# 03_-_CONNECTOR.net
KiCad netlist of a schematic drawn in Altium Designer
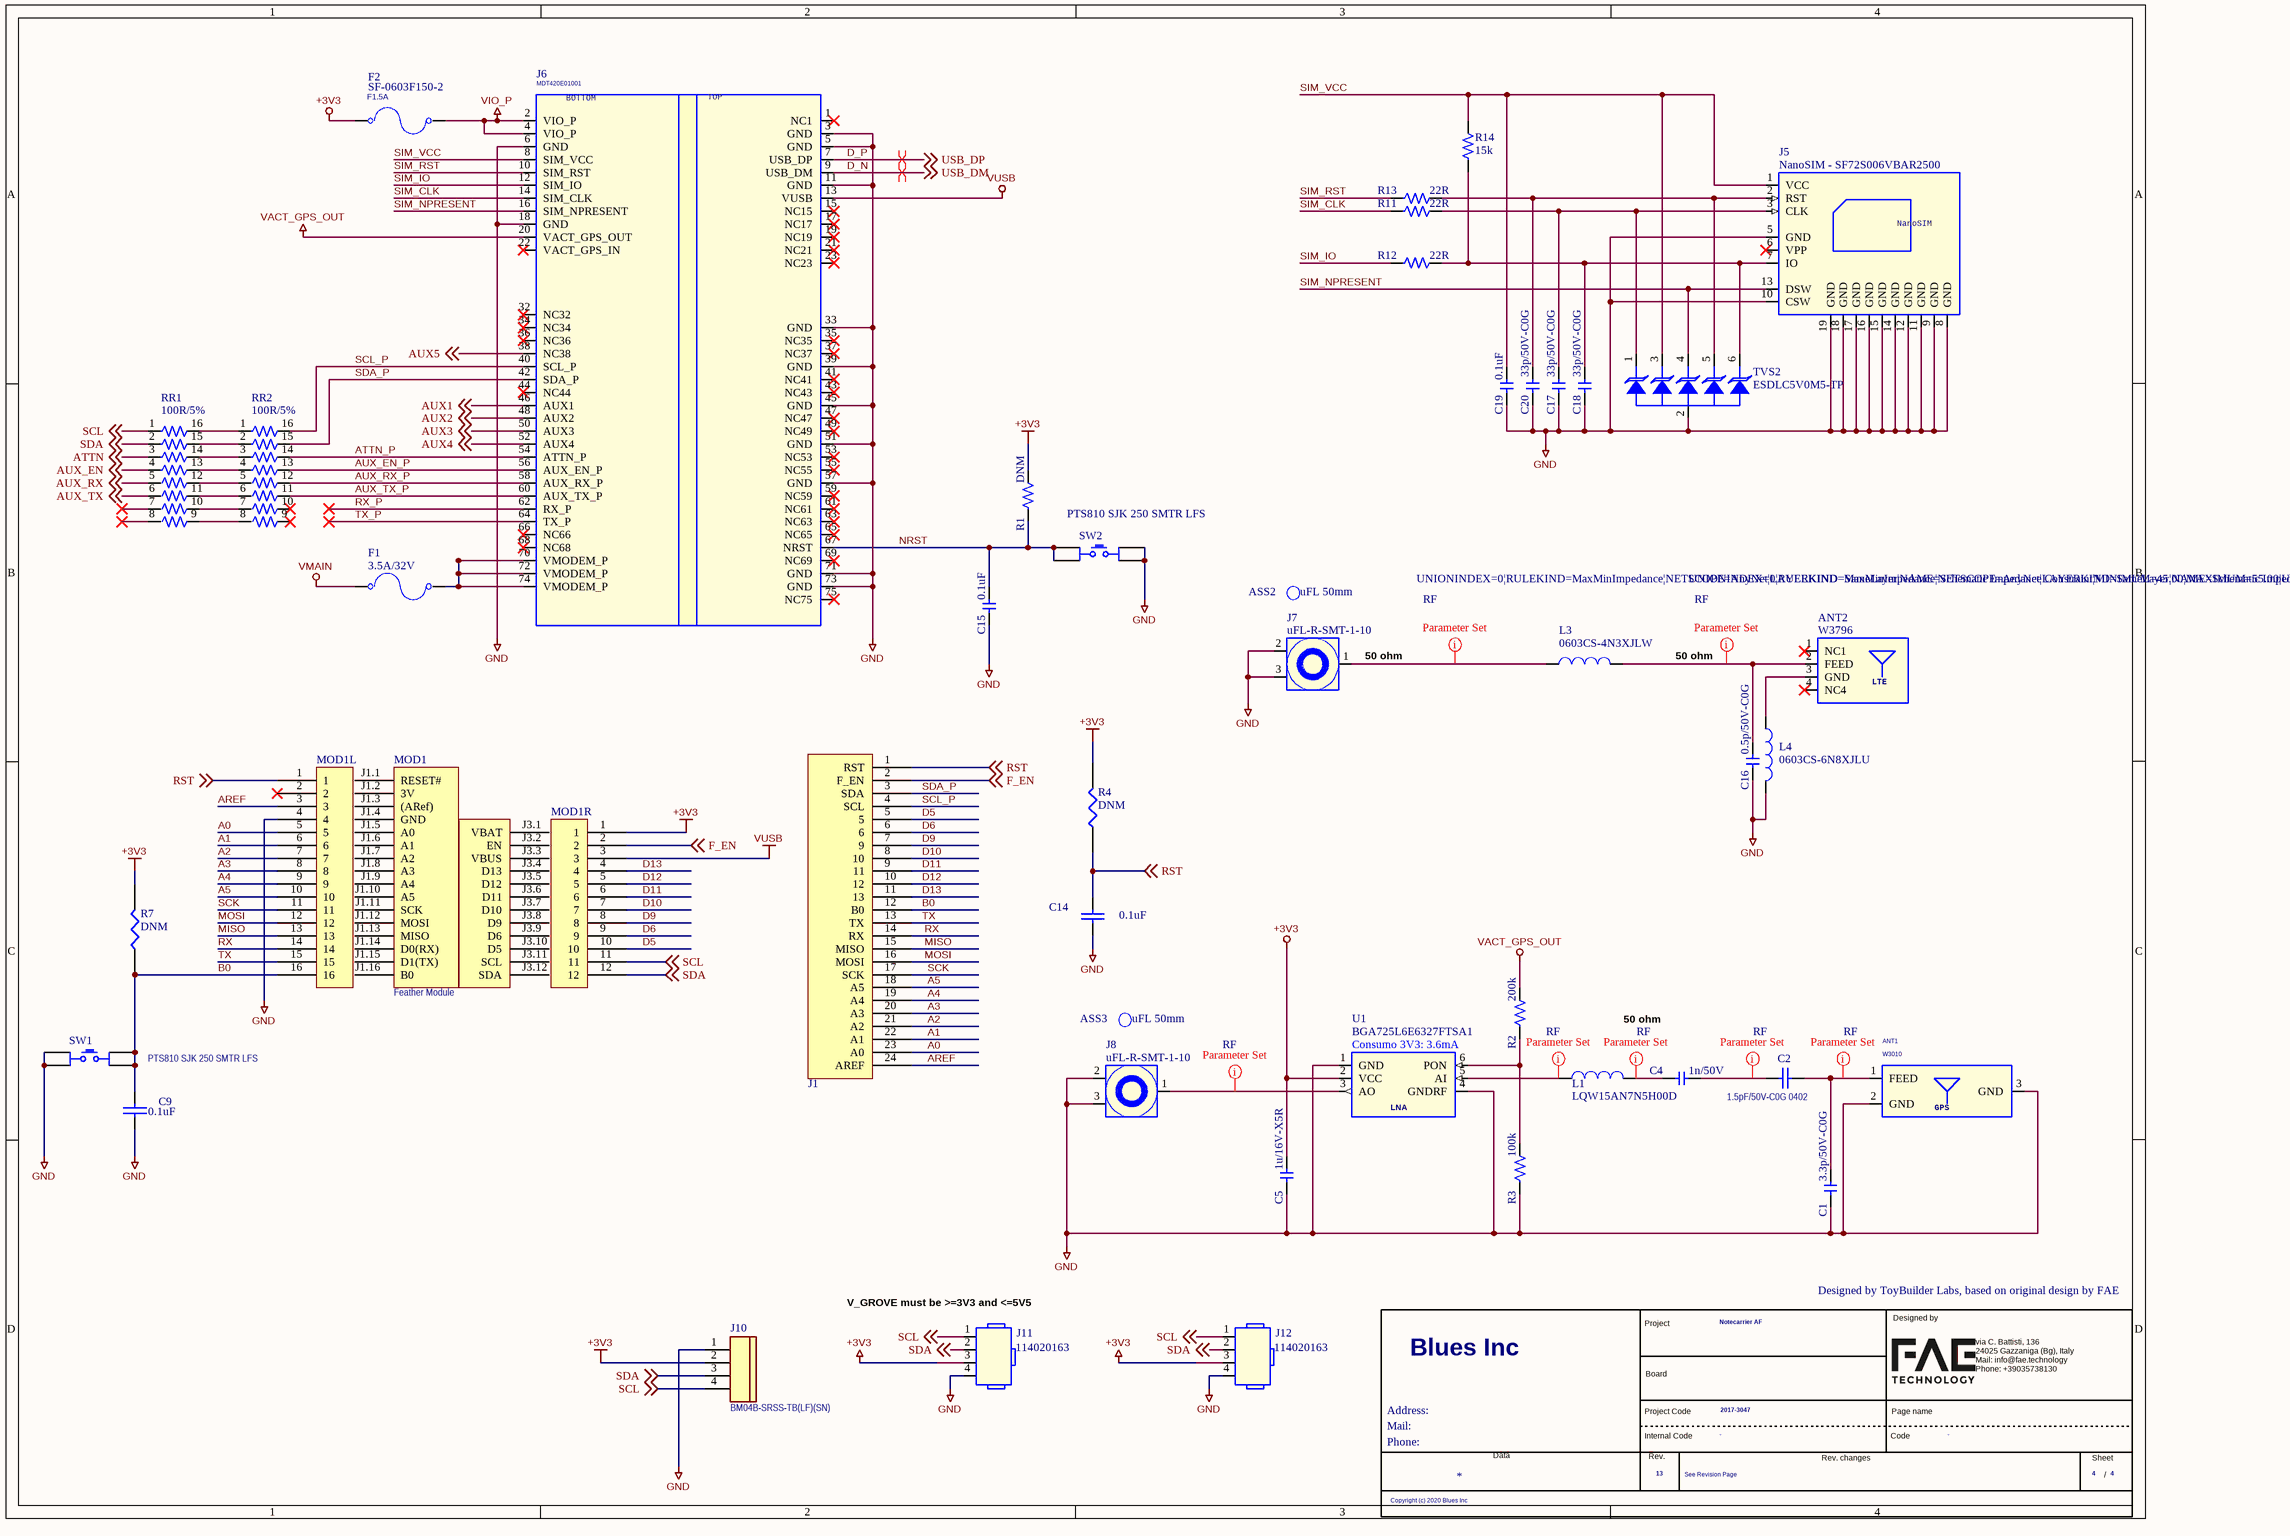
[diagram p0: 03 - CONNECTOR.SchDoc]

(export (version "E")
  (design (tool "Eeschema 10.0.6"))
  (components
    (comp (ref "*")
      (value "MyBlues")
      (fields
        (field (name "ADDRESS") "Address:")
        (field (name "COPYRIGHT") "Copyright (c) 2020 Blues Inc")
        (field (name "CUSTOMER CODE") "-")
        (field (name "CUSTOMERNAME") "Blues Inc")
        (field (name "DATABASE") "-")
        (field (name "DOCUMENTOREV") "See Revision Page")
        (field (name "MAIL") "Mail:")
        (field (name "NOME PROGETTO") "Notecarrier AF")
        (field (name "PAGE COUNT") "4")
        (field (name "PAGE NUMBER") "4")
        (field (name "PHONE") "Phone:")
        (field (name "PROJECT CODE") "2017-3047")
        (field (name "REVISION") "13")
      )
      (libsource (lib "*") (part "MyBlues"))
    )
    (comp (ref "ANT1")
      (value "W3010")
      (footprint "ANT-W3010")
      (description "ANTENNA CHIP 1.575GHZ D=3.2X10X2 W3010 PULSE SMT")
      (libsource (lib "*") (part "ANT - W3010 - GPS-GLONASS"))
    )
    (comp (ref "ANT2")
      (value "W3796")
      (footprint "ANT-W3796")
      (description "ANTENNA CHIP LTE D=40X7X3 W3796 PULSE SMT")
      (libsource (lib "*") (part "ANT - W3796 - LTE"))
    )
    (comp (ref "ASS2")
      (value "uFL 50mm")
      (description "CAVO COAX uFl-uFl 415-0086-050 HIROSE CINCH CONNECTIVITY SOLUTIONS JOHNSON")
      (libsource (lib "*") (part "0000_BASE SIMBOLO_OBJ"))
    )
    (comp (ref "ASS3")
      (value "uFL 50mm")
      (description "CAVO COAX uFl-uFl 415-0086-050 HIROSE CINCH CONNECTIVITY SOLUTIONS JOHNSON")
      (libsource (lib "*") (part "0000_BASE SIMBOLO_OBJ"))
    )
    (comp (ref "C1")
      (value "3.3p/50V-C0G")
      (footprint "CS-C-0402")
      (description "CHIP CAP.CER. 3.3pF 50V 5% C0G 0402")
      (libsource (lib "*") (part "CS-C-0402-3.3p/50V-C0G"))
    )
    (comp (ref "C2")
      (value "1.5pF/50V-C0G 0402")
      (footprint "CAPC1005X55X25NL05T10")
      (fields (field (name "PART NUMBER") "GJM1555C1H1R5BB01D") (field (name "MANUFACTURER") "Murata"))
      (libsource (lib "Altium Content Vault") (part "CAP"))
    )
    (comp (ref "C4")
      (value "1n/50V")
      (footprint "CS-C-0402")
      (description "CHIP CAP.CER. 1nF 50V 10% X7R 0402")
      (libsource (lib "*") (part "CS-C-0402-1n/50V"))
    )
    (comp (ref "C5")
      (value "1u/16V-X5R")
      (footprint "CS-C-0402")
      (description "CHIP CAP.CER. 1uF 16V 10% X5R 0402")
      (libsource (lib "*") (part "CS-C-0402-1u/16-X5R"))
    )
    (comp (ref "C9")
      (value "0.1uF")
      (footprint "CS-C-0402")
      (description "CHIP CAP.CER. 100nF 16V 10% X7R 0402")
      (fields (field (name "MFR") "Yageo"))
      (libsource (lib "Cap_SCH") (part "CAP"))
    )
    (comp (ref "C14")
      (value "0.1uF")
      (footprint "CS-C-0402")
      (description "CHIP CAP.CER. 100nF 16V 10% X7R 0402")
      (fields (field (name "MFR") "Yageo"))
      (libsource (lib "Cap_SCH") (part "CAP"))
    )
    (comp (ref "C15")
      (value "0.1uF")
      (footprint "CS-C-0402")
      (description "CHIP CAP.CER. 100nF 16V 10% X7R 0402")
      (fields (field (name "MFR") "Yageo"))
      (libsource (lib "*") (part "CS-C-0402-100n/16V"))
    )
    (comp (ref "C16")
      (value "0.5p/50V-C0G")
      (footprint "CS-C-0402")
      (description "CHIP CAP.CER. 0.5pF 50V ±0.25 C0G 0402 GRM1555C1HR50CA01D MURATA")
      (libsource (lib "*") (part "CS-C-0402-0.5p/50V-C0G"))
    )
    (comp (ref "C17")
      (value "33p/50V-C0G")
      (footprint "CS-C-0402")
      (description "CHIP CAP.CER. 33pF 50V 5% C0G 0402")
      (libsource (lib "*") (part "CS-C-0402-33p/50V-C0G"))
    )
    (comp (ref "C18")
      (value "33p/50V-C0G")
      (footprint "CS-C-0402")
      (description "CHIP CAP.CER. 33pF 50V 5% C0G 0402")
      (libsource (lib "*") (part "CS-C-0402-33p/50V-C0G"))
    )
    (comp (ref "C19")
      (value "0.1uF")
      (footprint "CS-C-0402")
      (description "CHIP CAP.CER. 100nF 16V 10% X7R 0402")
      (fields (field (name "MFR") "Yageo"))
      (libsource (lib "*") (part "CS-C-0402-100n/16V"))
    )
    (comp (ref "C20")
      (value "33p/50V-C0G")
      (footprint "CS-C-0402")
      (description "CHIP CAP.CER. 33pF 50V 5% C0G 0402")
      (libsource (lib "*") (part "CS-C-0402-33p/50V-C0G"))
    )
    (comp (ref "F1")
      (value "3.5A/32V")
      (footprint "FS-0603")
      (description "FUSIBILE RAPIDO 3.5A 32V 0603 0603SFV350F/32-2 LITTELFUSE SMT")
      (fields (field (name "MPN") "0603SFV350F/32-2"))
      (libsource (lib "*") (part "RAPIDO - 0603SFV350F- 3.5A/32V"))
    )
    (comp (ref "F2")
      (value "SF-0603F150-2")
      (footprint "FS-0603")
      (description "FUSIBILE RAPIDO 1.5A 32V 0603 SF-0603F150-2 BOURNS SMT")
      (libsource (lib "*") (part "RAPIDO - SF-0603F150-2-1.5A/32V"))
    )
    (comp (ref "J1")
      (value "12X1")
      (footprint "WE24S - 2.54")
      (libsource (lib "ATA_BLS_002_NTCR_A0-01_SCHLIB") (part "SIDECON"))
    )
    (comp (ref "J5")
      (value "NanoSIM - SF72S006VBAR2500")
      (footprint "J-NANOSIM-SF72S006VBA")
      (description "CONN. NANOSIM 8P F/90° PUSH-PUSH SF72S006VBAR2500 JAE ELECTRONICS SMT")
      (libsource (lib "*") (part "NANOSIM - J-NANOSIM-SF72S006VBA"))
    )
    (comp (ref "J6")
      (value "MDT420E01001")
      (footprint "J-75-0050-MOS-M2-E")
      (description "CONN. M.2 75P M/90° P=0.5 MDT420E01001 AMPHENOL SMT")
      (libsource (lib "*") (part "AMPHENOL-75 - M-2 KEY E_13"))
    )
    (comp (ref "J7")
      (value "uFL-R-SMT-1-10")
      (footprint "J-3-MDS-UFL")
      (description "CONN. RF M U.FL-R-SMT-1(10) HIROSE SMT")
      (libsource (lib "*") (part "UFL - U-FL-R-SMT-1-10"))
    )
    (comp (ref "J8")
      (value "uFL-R-SMT-1-10")
      (footprint "J-3-MDS-UFL")
      (description "CONN. RF M U.FL-R-SMT-1(10) HIROSE SMT")
      (libsource (lib "*") (part "UFL - U-FL-R-SMT-1-10"))
    )
    (comp (ref "J10")
      (value "BM04B-SRSS-TB(LF)(SN)")
      (footprint "JST_BM04B-SRSS-TB")
      (description "Wire-to-board, 1mm, SMT Vert, 4POS")
      (fields (field (name "MANUFACTURER") "JST"))
      (libsource (lib "TBL Connectors") (part "JST_BM04B-SRSS-TB"))
    )
    (comp (ref "J11")
      (value "114020163")
      (footprint "J-4-0200-MDS-GROVE")
      (description "CONN. GROVE 4P M/D P=2 114020163 SEEDSTUDIO SMT")
      (libsource (lib "*") (part "GROVE - J-4-0200-MDS-GROVE"))
    )
    (comp (ref "J12")
      (value "114020163")
      (footprint "J-4-0200-MDS-GROVE")
      (description "CONN. GROVE 4P M/D P=2 114020163 SEEDSTUDIO SMT")
      (libsource (lib "*") (part "GROVE - J-4-0200-MDS-GROVE"))
    )
    (comp (ref "L1")
      (value "LQW15AN7N5H00D")
      (footprint "LS-0402")
      (description "INDUTTANZA 7.5nH 0.57A 3% A FILO 0402 LQW15AN7N5H00D MURATA SMT")
      (libsource (lib "*") (part "L - LQW15AN7N5H00D - 7.5n/0.57A"))
    )
    (comp (ref "L3")
      (value "0603CS-4N3XJLW")
      (footprint "LS-0603CS")
      (description "INDUTTANZA 4.3nH 0.7A 5% 0603 0603CS-4N3XJLW COILCRAFT SMT")
      (libsource (lib "*") (part "L - 0603CS-4N3XJLW-4.3n/0.7A"))
    )
    (comp (ref "L4")
      (value "0603CS-6N8XJLU")
      (footprint "LS-0603CS")
      (description "INDUTTANZA 6.8nH 0.7A 5% 0603 0603CS-6N8XJLU COILCRAFT SMT")
      (libsource (lib "*") (part "L - 0603CS-6N8XJLU-6.8n/0.7A"))
    )
    (comp (ref "MOD1")
      (value "Feather Module")
      (footprint "FEATHER_COMMON_MOUNTING")
      (description "Socket Footprint for Typical Adafruit Feather Module, SMT socket type")
      (libsource (lib "Notebox Integrated Library") (part "FEATHER_COMMON_MOUNTING"))
    )
    (comp (ref "MOD1L")
      (value "Socket 16-Pin, 0.100 inch (0.335 inch body)")
      (footprint "SOCKET_LFB_16")
      (description "Socket 16-Pin, 0.100 in")
      (libsource (lib "TBLI-Headers") (part "SOCKET_LFB_16"))
    )
    (comp (ref "MOD1R")
      (value "Socket 12-Pin, 0.100 inch (0.335 inch body)")
      (footprint "SOCKET_LFB_12")
      (description "Socket 12-Pin, 0.100 in")
      (libsource (lib "TBLI-Headers") (part "SOCKET_LFB_12"))
    )
    (comp (ref "R1")
      (value "DNM")
      (footprint "RS-0402")
      (description "CHIP RES. 1K 0402 1/16W 1%")
      (libsource (lib "*") (part "RS-0402-1k"))
    )
    (comp (ref "R2")
      (value "200k")
      (footprint "RS-0402")
      (description "CHIP RES. 200K 0402 1/16W 1%")
      (libsource (lib "*") (part "RS-0402-200k"))
    )
    (comp (ref "R3")
      (value "100k")
      (footprint "RS-0402")
      (description "CHIP RES. 100K 0402 1/16W 1%")
      (libsource (lib "*") (part "RS-0402-100k"))
    )
    (comp (ref "R4")
      (value "DNM")
      (footprint "RS-0402")
      (description "SMD Resistors")
      (libsource (lib "Res_SCH") (part "R1_S"))
    )
    (comp (ref "R7")
      (value "DNM")
      (footprint "RS-0402")
      (description "SMD Resistors")
      (libsource (lib "Res_SCH") (part "R1_S"))
    )
    (comp (ref "R11")
      (value "22R")
      (footprint "RS-0603")
      (description "CHIP RES. 22R 0603 1/16W 1%")
      (libsource (lib "*") (part "RS-0603-22r"))
    )
    (comp (ref "R12")
      (value "22R")
      (footprint "RS-0603")
      (description "CHIP RES. 22R 0603 1/16W 1%")
      (libsource (lib "*") (part "RS-0603-22r"))
    )
    (comp (ref "R13")
      (value "22R")
      (footprint "RS-0603")
      (description "CHIP RES. 22R 0603 1/16W 1%")
      (libsource (lib "*") (part "RS-0603-22r"))
    )
    (comp (ref "R14")
      (value "15k")
      (footprint "RS-0402")
      (description "CHIP RES. 15K 0402 1/16W 1%")
      (libsource (lib "*") (part "RS-0402-15k"))
    )
    (comp (ref "RR1")
      (value "100R/5%")
      (footprint "RR-8X-1506")
      (description "RETE RESISTIVA 8R sing. 100R 5% 1506 CONVEX CAY16-101J8LF BOURNS SMT")
      (libsource (lib "*") (part "RR-8X-1506-100r/5%"))
    )
    (comp (ref "RR2")
      (value "100R/5%")
      (footprint "RR-8X-1506")
      (description "RETE RESISTIVA 8R sing. 100R 5% 1506 CONVEX CAY16-101J8LF BOURNS SMT")
      (libsource (lib "*") (part "RR-8X-1506-100r/5%"))
    )
    (comp (ref "SW1")
      (value "PTS810 SJK 250 SMTR LFS")
      (footprint "CK-PTS810-SJx")
      (description "SWITCH TACTILE SPST-NO 0.05A 12V 4.2 mm x 3.2 mm")
      (fields (field (name "MANUFACTURER") "C&K"))
      (libsource (lib "TBL Switches and Buttons") (part "CK_PTS810 SJK 250 SMTR LFS"))
    )
    (comp (ref "SW2")
      (value "PTS810 SJK 250 SMTR LFS")
      (footprint "CK-PTS810-SJx")
      (description "SWITCH TACTILE SPST-NO 0.05A 12V 4.2 mm x 3.2 mm")
      (fields (field (name "MANUFACTURER") "C&K"))
      (libsource (lib "TBL Switches and Buttons") (part "CK_PTS810 SJK 250 SMTR LFS"))
    )
    (comp (ref "TVS2")
      (value "ESDLC5V0M5-TP")
      (footprint "SOT666")
      (description "DIODO TVS TRANSIL UNIDIR. 20W 5V ESDLC5V0M5-TP SOT563 SMT")
      (libsource (lib "*") (part "TVS-UNI5x - ESDLC5V0M5-TP - 5V"))
    )
    (comp (ref "U1")
      (value "BGA725L6E6327FTSA1")
      (footprint "XFDFN6")
      (description "INTEGRATO BGA725L6E6327FTSA1 INFINEON TSLP-6 SMT")
      (fields (field (name "CONSUMO") "Consumo 3V3: 3.6mA"))
      (libsource (lib "*") (part "LNA-RF - BGA725L6E6327FTSA1"))
    )
  )
  (nets
    (net (code "1") (name "+3V3") (class "Default")
      (node (ref "C5") (pin "1") (pinfunction "1_1") (pintype "passive"))
      (node (ref "F2") (pin "1") (pinfunction "1_1") (pintype "passive"))
      (node (ref "J10") (pin "2") (pinfunction "2_2") (pintype "passive"))
      (node (ref "J11") (pin "3") (pinfunction "3_3") (pintype "passive"))
      (node (ref "J12") (pin "3") (pinfunction "3_3") (pintype "passive"))
      (node (ref "MOD1R") (pin "1") (pinfunction "1_1") (pintype "passive"))
      (node (ref "R1") (pin "2") (pinfunction "2_2") (pintype "passive"))
      (node (ref "R4") (pin "2") (pinfunction "2_2") (pintype "passive"))
      (node (ref "R7") (pin "2") (pinfunction "2_2") (pintype "passive"))
      (node (ref "U1") (pin "2") (pinfunction "VCC_2") (pintype "power_in"))
    )
    (net (code "2") (name "/A0") (class "Default")
      (node (ref "J1") (pin "23") (pinfunction "A0_23") (pintype "passive"))
      (node (ref "MOD1L") (pin "5") (pinfunction "5_5") (pintype "passive"))
    )
    (net (code "3") (name "/A1") (class "Default")
      (node (ref "J1") (pin "22") (pinfunction "A1_22") (pintype "passive"))
      (node (ref "MOD1L") (pin "6") (pinfunction "6_6") (pintype "passive"))
    )
    (net (code "4") (name "/A2") (class "Default")
      (node (ref "J1") (pin "21") (pinfunction "A2_21") (pintype "passive"))
      (node (ref "MOD1L") (pin "7") (pinfunction "7_7") (pintype "passive"))
    )
    (net (code "5") (name "/A3") (class "Default")
      (node (ref "J1") (pin "20") (pinfunction "A3_20") (pintype "passive"))
      (node (ref "MOD1L") (pin "8") (pinfunction "8_8") (pintype "passive"))
    )
    (net (code "6") (name "/A4") (class "Default")
      (node (ref "J1") (pin "19") (pinfunction "A4_19") (pintype "passive"))
      (node (ref "MOD1L") (pin "9") (pinfunction "9_9") (pintype "passive"))
    )
    (net (code "7") (name "/A5") (class "Default")
      (node (ref "J1") (pin "18") (pinfunction "A5_18") (pintype "passive"))
      (node (ref "MOD1L") (pin "10") (pinfunction "10_10") (pintype "passive"))
    )
    (net (code "8") (name "/AREF") (class "Default")
      (node (ref "J1") (pin "24") (pinfunction "AREF_24") (pintype "passive"))
      (node (ref "MOD1L") (pin "3") (pinfunction "3_3") (pintype "passive"))
    )
    (net (code "9") (name "/ATTN_P") (class "Default")
      (node (ref "J6") (pin "54") (pinfunction "ATTN_P_54") (pintype "passive"))
      (node (ref "RR2") (pin "14") (pinfunction "14_14") (pintype "passive"))
    )
    (net (code "10") (name "/AUX_EN_P") (class "Default")
      (node (ref "J6") (pin "56") (pinfunction "AUX_EN_P_56") (pintype "passive"))
      (node (ref "RR2") (pin "13") (pinfunction "13_13") (pintype "passive"))
    )
    (net (code "11") (name "/AUX_RX_P") (class "Default")
      (node (ref "J6") (pin "58") (pinfunction "AUX_RX_P_58") (pintype "passive"))
      (node (ref "RR2") (pin "12") (pinfunction "12_12") (pintype "passive"))
    )
    (net (code "12") (name "/AUX_TX_P") (class "Default")
      (node (ref "J6") (pin "60") (pinfunction "AUX_TX_P_60") (pintype "passive"))
      (node (ref "RR2") (pin "11") (pinfunction "11_11") (pintype "passive"))
    )
    (net (code "13") (name "/B0") (class "Default")
      (node (ref "C9") (pin "1") (pinfunction "1_1") (pintype "passive"))
      (node (ref "J1") (pin "12") (pinfunction "B0_12") (pintype "passive"))
      (node (ref "MOD1L") (pin "16") (pinfunction "16_16") (pintype "passive"))
      (node (ref "R7") (pin "1") (pinfunction "1_1") (pintype "passive"))
      (node (ref "SW1") (pin "1") (pinfunction "1_1") (pintype "passive"))
      (node (ref "SW1") (pin "2") (pinfunction "2_2") (pintype "passive"))
    )
    (net (code "14") (name "/D5") (class "Default")
      (node (ref "J1") (pin "5") (pinfunction "5_5") (pintype "passive"))
      (node (ref "MOD1R") (pin "10") (pinfunction "10_10") (pintype "passive"))
    )
    (net (code "15") (name "/D6") (class "Default")
      (node (ref "J1") (pin "6") (pinfunction "6_6") (pintype "passive"))
      (node (ref "MOD1R") (pin "9") (pinfunction "9_9") (pintype "passive"))
    )
    (net (code "16") (name "/D9") (class "Default")
      (node (ref "J1") (pin "7") (pinfunction "9_7") (pintype "passive"))
      (node (ref "MOD1R") (pin "8") (pinfunction "8_8") (pintype "passive"))
    )
    (net (code "17") (name "/D10") (class "Default")
      (node (ref "J1") (pin "8") (pinfunction "10_8") (pintype "passive"))
      (node (ref "MOD1R") (pin "7") (pinfunction "7_7") (pintype "passive"))
    )
    (net (code "18") (name "/D11") (class "Default")
      (node (ref "J1") (pin "9") (pinfunction "11_9") (pintype "passive"))
      (node (ref "MOD1R") (pin "6") (pinfunction "6_6") (pintype "passive"))
    )
    (net (code "19") (name "/D12") (class "Default")
      (node (ref "J1") (pin "10") (pinfunction "12_10") (pintype "passive"))
      (node (ref "MOD1R") (pin "5") (pinfunction "5_5") (pintype "passive"))
    )
    (net (code "20") (name "/D13") (class "Default")
      (node (ref "J1") (pin "11") (pinfunction "13_11") (pintype "passive"))
      (node (ref "MOD1R") (pin "4") (pinfunction "4_4") (pintype "passive"))
    )
    (net (code "21") (name "/MISO") (class "Default")
      (node (ref "J1") (pin "15") (pinfunction "MISO_15") (pintype "passive"))
      (node (ref "MOD1L") (pin "13") (pinfunction "13_13") (pintype "passive"))
    )
    (net (code "22") (name "/MOSI") (class "Default")
      (node (ref "J1") (pin "16") (pinfunction "MOSI_16") (pintype "passive"))
      (node (ref "MOD1L") (pin "12") (pinfunction "12_12") (pintype "passive"))
    )
    (net (code "23") (name "/NRST") (class "Default")
      (node (ref "C15") (pin "1") (pinfunction "1_1") (pintype "passive"))
      (node (ref "J6") (pin "67") (pinfunction "NRST_67") (pintype "passive"))
      (node (ref "R1") (pin "1") (pinfunction "1_1") (pintype "passive"))
      (node (ref "SW2") (pin "3") (pinfunction "3_3") (pintype "passive"))
      (node (ref "SW2") (pin "4") (pinfunction "4_4") (pintype "passive"))
    )
    (net (code "24") (name "/RX") (class "Default")
      (node (ref "J1") (pin "14") (pinfunction "RX_14") (pintype "passive"))
      (node (ref "MOD1L") (pin "14") (pinfunction "14_14") (pintype "passive"))
    )
    (net (code "25") (name "/RX_P") (class "Default")
      (node (ref "J6") (pin "62") (pinfunction "RX_P_62") (pintype "passive+no_connect"))
    )
    (net (code "26") (name "/SCK") (class "Default")
      (node (ref "J1") (pin "17") (pinfunction "SCK_17") (pintype "passive"))
      (node (ref "MOD1L") (pin "11") (pinfunction "11_11") (pintype "passive"))
    )
    (net (code "27") (name "/SCL_P") (class "Default")
      (node (ref "J1") (pin "4") (pinfunction "SCL_4") (pintype "passive"))
      (node (ref "J6") (pin "40") (pinfunction "SCL_P_40") (pintype "passive"))
      (node (ref "RR2") (pin "16") (pinfunction "16_16") (pintype "passive"))
    )
    (net (code "28") (name "/SDA_P") (class "Default")
      (node (ref "J1") (pin "3") (pinfunction "SDA_3") (pintype "passive"))
      (node (ref "J6") (pin "42") (pinfunction "SDA_P_42") (pintype "passive"))
      (node (ref "RR2") (pin "15") (pinfunction "15_15") (pintype "passive"))
    )
    (net (code "29") (name "/SIM_CLK") (class "Default")
      (node (ref "J6") (pin "14") (pinfunction "SIM_CLK_14") (pintype "passive"))
      (node (ref "R11") (pin "1") (pinfunction "1_1") (pintype "passive"))
    )
    (net (code "30") (name "/SIM_IO") (class "Default")
      (node (ref "J6") (pin "12") (pinfunction "SIM_IO_12") (pintype "passive"))
      (node (ref "R12") (pin "1") (pinfunction "1_1") (pintype "passive"))
    )
    (net (code "31") (name "/SIM_NPRESENT") (class "Default")
      (node (ref "J5") (pin "13") (pinfunction "DSW_13") (pintype "passive"))
      (node (ref "J6") (pin "16") (pinfunction "SIM_NPRESENT_16") (pintype "passive"))
      (node (ref "TVS2") (pin "4") (pinfunction "C4_4") (pintype "passive"))
    )
    (net (code "32") (name "/SIM_RST") (class "Default")
      (node (ref "J6") (pin "10") (pinfunction "SIM_RST_10") (pintype "passive"))
      (node (ref "R13") (pin "1") (pinfunction "1_1") (pintype "passive"))
    )
    (net (code "33") (name "/SIM_VCC") (class "Default")
      (node (ref "C19") (pin "1") (pinfunction "1_1") (pintype "passive"))
      (node (ref "J5") (pin "1") (pinfunction "VCC_1") (pintype "power_in"))
      (node (ref "J6") (pin "8") (pinfunction "SIM_VCC_8") (pintype "passive"))
      (node (ref "R14") (pin "2") (pinfunction "2_2") (pintype "passive"))
      (node (ref "TVS2") (pin "3") (pinfunction "C3_3") (pintype "passive"))
    )
    (net (code "34") (name "/TX") (class "Default")
      (node (ref "J1") (pin "13") (pinfunction "TX_13") (pintype "passive"))
      (node (ref "MOD1L") (pin "15") (pinfunction "15_15") (pintype "passive"))
    )
    (net (code "35") (name "/TX_P") (class "Default")
      (node (ref "J6") (pin "64") (pinfunction "TX_P_64") (pintype "passive+no_connect"))
    )
    (net (code "36") (name "ATTN") (class "Default")
      (node (ref "RR1") (pin "3") (pinfunction "3_3") (pintype "passive"))
    )
    (net (code "37") (name "AUX1") (class "Default")
      (node (ref "J6") (pin "46") (pinfunction "AUX1_46") (pintype "passive"))
    )
    (net (code "38") (name "AUX2") (class "Default")
      (node (ref "J6") (pin "48") (pinfunction "AUX2_48") (pintype "passive"))
    )
    (net (code "39") (name "AUX3") (class "Default")
      (node (ref "J6") (pin "50") (pinfunction "AUX3_50") (pintype "passive"))
    )
    (net (code "40") (name "AUX4") (class "Default")
      (node (ref "J6") (pin "52") (pinfunction "AUX4_52") (pintype "passive"))
    )
    (net (code "41") (name "AUX5") (class "Default")
      (node (ref "J6") (pin "38") (pinfunction "NC38_38") (pintype "passive"))
    )
    (net (code "42") (name "AUX_EN") (class "Default")
      (node (ref "RR1") (pin "4") (pinfunction "4_4") (pintype "passive"))
    )
    (net (code "43") (name "AUX_RX") (class "Default")
      (node (ref "RR1") (pin "5") (pinfunction "5_5") (pintype "passive"))
    )
    (net (code "44") (name "AUX_TX") (class "Default")
      (node (ref "RR1") (pin "6") (pinfunction "6_6") (pintype "passive"))
    )
    (net (code "45") (name "F_EN") (class "Default")
      (node (ref "J1") (pin "2") (pinfunction "F_EN_2") (pintype "passive"))
      (node (ref "MOD1R") (pin "2") (pinfunction "2_2") (pintype "passive"))
    )
    (net (code "46") (name "GND") (class "Default")
      (node (ref "ANT1") (pin "2") (pinfunction "GND_2") (pintype "power_in"))
      (node (ref "ANT1") (pin "3") (pinfunction "GND_3") (pintype "power_in"))
      (node (ref "C1") (pin "2") (pinfunction "2_2") (pintype "passive"))
      (node (ref "C14") (pin "2") (pinfunction "2_2") (pintype "passive"))
      (node (ref "C15") (pin "2") (pinfunction "2_2") (pintype "passive"))
      (node (ref "C16") (pin "2") (pinfunction "2_2") (pintype "passive"))
      (node (ref "C17") (pin "2") (pinfunction "2_2") (pintype "passive"))
      (node (ref "C18") (pin "2") (pinfunction "2_2") (pintype "passive"))
      (node (ref "C19") (pin "2") (pinfunction "2_2") (pintype "passive"))
      (node (ref "C20") (pin "2") (pinfunction "2_2") (pintype "passive"))
      (node (ref "C5") (pin "2") (pinfunction "2_2") (pintype "passive"))
      (node (ref "C9") (pin "2") (pinfunction "2_2") (pintype "passive"))
      (node (ref "J10") (pin "1") (pinfunction "1_1") (pintype "passive"))
      (node (ref "J11") (pin "4") (pinfunction "4_4") (pintype "passive"))
      (node (ref "J12") (pin "4") (pinfunction "4_4") (pintype "passive"))
      (node (ref "J5") (pin "10") (pinfunction "CSW_10") (pintype "passive"))
      (node (ref "J5") (pin "11") (pinfunction "GND_11") (pintype "power_in"))
      (node (ref "J5") (pin "12") (pinfunction "GND_12") (pintype "power_in"))
      (node (ref "J5") (pin "14") (pinfunction "GND_14") (pintype "power_in"))
      (node (ref "J5") (pin "15") (pinfunction "GND_15") (pintype "power_in"))
      (node (ref "J5") (pin "16") (pinfunction "GND_16") (pintype "power_in"))
      (node (ref "J5") (pin "17") (pinfunction "GND_17") (pintype "power_in"))
      (node (ref "J5") (pin "18") (pinfunction "GND_18") (pintype "power_in"))
      (node (ref "J5") (pin "19") (pinfunction "GND_19") (pintype "power_in"))
      (node (ref "J5") (pin "5") (pinfunction "GND_5") (pintype "power_in"))
      (node (ref "J5") (pin "8") (pinfunction "GND_8") (pintype "power_in"))
      (node (ref "J5") (pin "9") (pinfunction "GND_9") (pintype "power_in"))
      (node (ref "J6") (pin "11") (pinfunction "GND_11") (pintype "power_in"))
      (node (ref "J6") (pin "18") (pinfunction "GND_18") (pintype "power_in"))
      (node (ref "J6") (pin "3") (pinfunction "GND_3") (pintype "power_in"))
      (node (ref "J6") (pin "33") (pinfunction "GND_33") (pintype "power_in"))
      (node (ref "J6") (pin "39") (pinfunction "GND_39") (pintype "power_in"))
      (node (ref "J6") (pin "45") (pinfunction "GND_45") (pintype "power_in"))
      (node (ref "J6") (pin "5") (pinfunction "GND_5") (pintype "power_in"))
      (node (ref "J6") (pin "51") (pinfunction "GND_51") (pintype "power_in"))
      (node (ref "J6") (pin "57") (pinfunction "GND_57") (pintype "power_in"))
      (node (ref "J6") (pin "6") (pinfunction "GND_6") (pintype "power_in"))
      (node (ref "J6") (pin "71") (pinfunction "GND_71") (pintype "power_in"))
      (node (ref "J6") (pin "73") (pinfunction "GND_73") (pintype "power_in"))
      (node (ref "J7") (pin "2") (pinfunction "2_2") (pintype "passive"))
      (node (ref "J7") (pin "3") (pinfunction "3_3") (pintype "passive"))
      (node (ref "J8") (pin "2") (pinfunction "2_2") (pintype "passive"))
      (node (ref "J8") (pin "3") (pinfunction "3_3") (pintype "passive"))
      (node (ref "L4") (pin "2") (pinfunction "A_2") (pintype "passive"))
      (node (ref "MOD1L") (pin "4") (pinfunction "4_4") (pintype "passive"))
      (node (ref "R3") (pin "1") (pinfunction "1_1") (pintype "passive"))
      (node (ref "SW1") (pin "3") (pinfunction "3_3") (pintype "passive"))
      (node (ref "SW1") (pin "4") (pinfunction "4_4") (pintype "passive"))
      (node (ref "SW2") (pin "1") (pinfunction "1_1") (pintype "passive"))
      (node (ref "SW2") (pin "2") (pinfunction "2_2") (pintype "passive"))
      (node (ref "TVS2") (pin "2") (pinfunction "A2_2") (pintype "passive"))
      (node (ref "U1") (pin "1") (pinfunction "GND_1") (pintype "power_in"))
      (node (ref "U1") (pin "4") (pinfunction "GNDRF_4") (pintype "power_in"))
    )
    (net (code "47") (name "Net-(ANT1-FEED)") (class "Default")
      (node (ref "ANT1") (pin "1") (pinfunction "FEED_1") (pintype "passive"))
      (node (ref "C1") (pin "1") (pinfunction "1_1") (pintype "passive"))
      (node (ref "C2") (pin "2") (pinfunction "2_2") (pintype "passive"))
    )
    (net (code "48") (name "Net-(ANT2-FEED)") (class "Default")
      (node (ref "ANT2") (pin "2") (pinfunction "FEED_2") (pintype "passive"))
      (node (ref "C16") (pin "1") (pinfunction "1_1") (pintype "passive"))
      (node (ref "L3") (pin "2") (pinfunction "A_2") (pintype "passive"))
    )
    (net (code "49") (name "Net-(ANT2-GND)") (class "Default")
      (node (ref "ANT2") (pin "3") (pinfunction "GND_3") (pintype "power_in"))
      (node (ref "L4") (pin "1") (pinfunction "C_1") (pintype "passive"))
    )
    (net (code "50") (name "Net-(C2-Pad1)") (class "Default")
      (node (ref "C2") (pin "1") (pinfunction "1_1") (pintype "passive"))
      (node (ref "C4") (pin "2") (pinfunction "2_2") (pintype "passive"))
    )
    (net (code "51") (name "Net-(F1-Pad2)") (class "Default")
      (node (ref "F1") (pin "2") (pinfunction "2_2") (pintype "passive"))
      (node (ref "J6") (pin "70") (pinfunction "VMODEM_P_70") (pintype "power_in"))
      (node (ref "J6") (pin "72") (pinfunction "VMODEM_P_72") (pintype "power_in"))
      (node (ref "J6") (pin "74") (pinfunction "VMODEM_P_74") (pintype "power_in"))
    )
    (net (code "52") (name "Net-(J5-CLK)") (class "Default")
      (node (ref "C17") (pin "1") (pinfunction "1_1") (pintype "passive"))
      (node (ref "J5") (pin "3") (pinfunction "CLK_3") (pintype "input"))
      (node (ref "R11") (pin "2") (pinfunction "2_2") (pintype "passive"))
      (node (ref "TVS2") (pin "1") (pinfunction "C1_1") (pintype "passive"))
    )
    (net (code "53") (name "Net-(J5-IO)") (class "Default")
      (node (ref "C18") (pin "1") (pinfunction "1_1") (pintype "passive"))
      (node (ref "J5") (pin "7") (pinfunction "IO_7") (pintype "bidirectional"))
      (node (ref "R12") (pin "2") (pinfunction "2_2") (pintype "passive"))
      (node (ref "R14") (pin "1") (pinfunction "1_1") (pintype "passive"))
      (node (ref "TVS2") (pin "6") (pinfunction "C6_6") (pintype "passive"))
    )
    (net (code "54") (name "Net-(J5-RST)") (class "Default")
      (node (ref "C20") (pin "1") (pinfunction "1_1") (pintype "passive"))
      (node (ref "J5") (pin "2") (pinfunction "RST_2") (pintype "input"))
      (node (ref "R13") (pin "2") (pinfunction "2_2") (pintype "passive"))
      (node (ref "TVS2") (pin "5") (pinfunction "A5_5") (pintype "passive"))
    )
    (net (code "55") (name "Net-(L1-A)") (class "Default")
      (node (ref "C4") (pin "1") (pinfunction "1_1") (pintype "passive"))
      (node (ref "L1") (pin "2") (pinfunction "A_2") (pintype "passive"))
    )
    (net (code "56") (name "Net-(L1-C)") (class "Default")
      (node (ref "L1") (pin "1") (pinfunction "C_1") (pintype "passive"))
      (node (ref "U1") (pin "5") (pinfunction "AI_5") (pintype "input"))
    )
    (net (code "57") (name "Net-(L3-C)") (class "Default")
      (node (ref "J7") (pin "1") (pinfunction "1_1") (pintype "passive"))
      (node (ref "L3") (pin "1") (pinfunction "C_1") (pintype "passive"))
    )
    (net (code "58") (name "Net-(RR1-Pad9)") (class "Default")
      (node (ref "RR1") (pin "9") (pinfunction "9_9") (pintype "passive"))
      (node (ref "RR2") (pin "8") (pinfunction "8_8") (pintype "passive"))
    )
    (net (code "59") (name "Net-(RR1-Pad10)") (class "Default")
      (node (ref "RR1") (pin "10") (pinfunction "10_10") (pintype "passive"))
      (node (ref "RR2") (pin "7") (pinfunction "7_7") (pintype "passive"))
    )
    (net (code "60") (name "Net-(RR1-Pad11)") (class "Default")
      (node (ref "RR1") (pin "11") (pinfunction "11_11") (pintype "passive"))
      (node (ref "RR2") (pin "6") (pinfunction "6_6") (pintype "passive"))
    )
    (net (code "61") (name "Net-(RR1-Pad12)") (class "Default")
      (node (ref "RR1") (pin "12") (pinfunction "12_12") (pintype "passive"))
      (node (ref "RR2") (pin "5") (pinfunction "5_5") (pintype "passive"))
    )
    (net (code "62") (name "Net-(RR1-Pad13)") (class "Default")
      (node (ref "RR1") (pin "13") (pinfunction "13_13") (pintype "passive"))
      (node (ref "RR2") (pin "4") (pinfunction "4_4") (pintype "passive"))
    )
    (net (code "63") (name "Net-(RR1-Pad14)") (class "Default")
      (node (ref "RR1") (pin "14") (pinfunction "14_14") (pintype "passive"))
      (node (ref "RR2") (pin "3") (pinfunction "3_3") (pintype "passive"))
    )
    (net (code "64") (name "Net-(RR1-Pad15)") (class "Default")
      (node (ref "RR1") (pin "15") (pinfunction "15_15") (pintype "passive"))
      (node (ref "RR2") (pin "2") (pinfunction "2_2") (pintype "passive"))
    )
    (net (code "65") (name "Net-(RR1-Pad16)") (class "Default")
      (node (ref "RR1") (pin "16") (pinfunction "16_16") (pintype "passive"))
      (node (ref "RR2") (pin "1") (pinfunction "1_1") (pintype "passive"))
    )
    (net (code "66") (name "Net-(U1-AO)") (class "Default")
      (node (ref "J8") (pin "1") (pinfunction "1_1") (pintype "passive"))
      (node (ref "U1") (pin "3") (pinfunction "AO_3") (pintype "output"))
    )
    (net (code "67") (name "Net-(U1-PON)") (class "Default")
      (node (ref "R2") (pin "1") (pinfunction "1_1") (pintype "passive"))
      (node (ref "R3") (pin "2") (pinfunction "2_2") (pintype "passive"))
      (node (ref "U1") (pin "6") (pinfunction "PON_6") (pintype "input"))
    )
    (net (code "68") (name "RST") (class "Default")
      (node (ref "C14") (pin "1") (pinfunction "1_1") (pintype "passive"))
      (node (ref "J1") (pin "1") (pinfunction "RST_1") (pintype "passive"))
      (node (ref "MOD1L") (pin "1") (pinfunction "1_1") (pintype "passive"))
      (node (ref "R4") (pin "1") (pinfunction "1_1") (pintype "passive"))
    )
    (net (code "69") (name "SCL") (class "Default")
      (node (ref "J10") (pin "4") (pinfunction "4_4") (pintype "passive"))
      (node (ref "J11") (pin "1") (pinfunction "1_1") (pintype "passive"))
      (node (ref "J12") (pin "1") (pinfunction "1_1") (pintype "passive"))
      (node (ref "MOD1R") (pin "11") (pinfunction "11_11") (pintype "passive"))
      (node (ref "RR1") (pin "1") (pinfunction "1_1") (pintype "passive"))
    )
    (net (code "70") (name "SDA") (class "Default")
      (node (ref "J10") (pin "3") (pinfunction "3_3") (pintype "passive"))
      (node (ref "J11") (pin "2") (pinfunction "2_2") (pintype "passive"))
      (node (ref "J12") (pin "2") (pinfunction "2_2") (pintype "passive"))
      (node (ref "MOD1R") (pin "12") (pinfunction "12_12") (pintype "passive"))
      (node (ref "RR1") (pin "2") (pinfunction "2_2") (pintype "passive"))
    )
    (net (code "71") (name "USB_DM") (class "Default")
      (node (ref "J6") (pin "9") (pinfunction "USB_DM_9") (pintype "passive"))
    )
    (net (code "72") (name "USB_DP") (class "Default")
      (node (ref "J6") (pin "7") (pinfunction "USB_DP_7") (pintype "passive"))
    )
    (net (code "73") (name "VACT_GPS_OUT") (class "Default")
      (node (ref "J6") (pin "20") (pinfunction "VACT_GPS_OUT_20") (pintype "power_in"))
      (node (ref "R2") (pin "2") (pinfunction "2_2") (pintype "passive"))
    )
    (net (code "74") (name "VIO_P") (class "Default")
      (node (ref "F2") (pin "2") (pinfunction "2_2") (pintype "passive"))
      (node (ref "J6") (pin "2") (pinfunction "VIO_P_2") (pintype "power_in"))
      (node (ref "J6") (pin "4") (pinfunction "VIO_P_4") (pintype "power_in"))
    )
    (net (code "75") (name "VMAIN") (class "Default")
      (node (ref "F1") (pin "1") (pinfunction "1_1") (pintype "passive"))
    )
    (net (code "76") (name "VUSB") (class "Default")
      (node (ref "J6") (pin "13") (pinfunction "VUSB_13") (pintype "power_in"))
      (node (ref "MOD1R") (pin "3") (pinfunction "3_3") (pintype "passive"))
    )
    (net (code "77") (name "unconnected-(ANT2-NC1-Pad1)") (class "Default")
      (node (ref "ANT2") (pin "1") (pinfunction "NC1_1") (pintype "passive+no_connect"))
    )
    (net (code "78") (name "unconnected-(ANT2-NC4-Pad4)") (class "Default")
      (node (ref "ANT2") (pin "4") (pinfunction "NC4_4") (pintype "passive+no_connect"))
    )
    (net (code "79") (name "unconnected-(J5-VPP-Pad6)") (class "Default")
      (node (ref "J5") (pin "6") (pinfunction "VPP_6") (pintype "passive+no_connect"))
    )
    (net (code "80") (name "unconnected-(J6-NC1-Pad1)") (class "Default")
      (node (ref "J6") (pin "1") (pinfunction "NC1_1") (pintype "passive+no_connect"))
    )
    (net (code "81") (name "unconnected-(J6-NC15-Pad15)") (class "Default")
      (node (ref "J6") (pin "15") (pinfunction "NC15_15") (pintype "passive+no_connect"))
    )
    (net (code "82") (name "unconnected-(J6-NC17-Pad17)") (class "Default")
      (node (ref "J6") (pin "17") (pinfunction "NC17_17") (pintype "passive+no_connect"))
    )
    (net (code "83") (name "unconnected-(J6-NC19-Pad19)") (class "Default")
      (node (ref "J6") (pin "19") (pinfunction "NC19_19") (pintype "passive+no_connect"))
    )
    (net (code "84") (name "unconnected-(J6-NC21-Pad21)") (class "Default")
      (node (ref "J6") (pin "21") (pinfunction "NC21_21") (pintype "passive+no_connect"))
    )
    (net (code "85") (name "unconnected-(J6-NC23-Pad23)") (class "Default")
      (node (ref "J6") (pin "23") (pinfunction "NC23_23") (pintype "passive+no_connect"))
    )
    (net (code "86") (name "unconnected-(J6-NC32-Pad32)") (class "Default")
      (node (ref "J6") (pin "32") (pinfunction "NC32_32") (pintype "passive+no_connect"))
    )
    (net (code "87") (name "unconnected-(J6-NC34-Pad34)") (class "Default")
      (node (ref "J6") (pin "34") (pinfunction "NC34_34") (pintype "passive+no_connect"))
    )
    (net (code "88") (name "unconnected-(J6-NC35-Pad35)") (class "Default")
      (node (ref "J6") (pin "35") (pinfunction "NC35_35") (pintype "passive+no_connect"))
    )
    (net (code "89") (name "unconnected-(J6-NC36-Pad36)") (class "Default")
      (node (ref "J6") (pin "36") (pinfunction "NC36_36") (pintype "passive+no_connect"))
    )
    (net (code "90") (name "unconnected-(J6-NC37-Pad37)") (class "Default")
      (node (ref "J6") (pin "37") (pinfunction "NC37_37") (pintype "passive+no_connect"))
    )
    (net (code "91") (name "unconnected-(J6-NC41-Pad41)") (class "Default")
      (node (ref "J6") (pin "41") (pinfunction "NC41_41") (pintype "passive+no_connect"))
    )
    (net (code "92") (name "unconnected-(J6-NC43-Pad43)") (class "Default")
      (node (ref "J6") (pin "43") (pinfunction "NC43_43") (pintype "passive+no_connect"))
    )
    (net (code "93") (name "unconnected-(J6-NC44-Pad44)") (class "Default")
      (node (ref "J6") (pin "44") (pinfunction "NC44_44") (pintype "passive+no_connect"))
    )
    (net (code "94") (name "unconnected-(J6-NC47-Pad47)") (class "Default")
      (node (ref "J6") (pin "47") (pinfunction "NC47_47") (pintype "passive+no_connect"))
    )
    (net (code "95") (name "unconnected-(J6-NC49-Pad49)") (class "Default")
      (node (ref "J6") (pin "49") (pinfunction "NC49_49") (pintype "passive+no_connect"))
    )
    (net (code "96") (name "unconnected-(J6-NC53-Pad53)") (class "Default")
      (node (ref "J6") (pin "53") (pinfunction "NC53_53") (pintype "passive+no_connect"))
    )
    (net (code "97") (name "unconnected-(J6-NC55-Pad55)") (class "Default")
      (node (ref "J6") (pin "55") (pinfunction "NC55_55") (pintype "passive+no_connect"))
    )
    (net (code "98") (name "unconnected-(J6-NC59-Pad59)") (class "Default")
      (node (ref "J6") (pin "59") (pinfunction "NC59_59") (pintype "passive+no_connect"))
    )
    (net (code "99") (name "unconnected-(J6-NC61-Pad61)") (class "Default")
      (node (ref "J6") (pin "61") (pinfunction "NC61_61") (pintype "passive+no_connect"))
    )
    (net (code "100") (name "unconnected-(J6-NC63-Pad63)") (class "Default")
      (node (ref "J6") (pin "63") (pinfunction "NC63_63") (pintype "passive+no_connect"))
    )
    (net (code "101") (name "unconnected-(J6-NC65-Pad65)") (class "Default")
      (node (ref "J6") (pin "65") (pinfunction "NC65_65") (pintype "passive+no_connect"))
    )
    (net (code "102") (name "unconnected-(J6-NC66-Pad66)") (class "Default")
      (node (ref "J6") (pin "66") (pinfunction "NC66_66") (pintype "passive+no_connect"))
    )
    (net (code "103") (name "unconnected-(J6-NC68-Pad68)") (class "Default")
      (node (ref "J6") (pin "68") (pinfunction "NC68_68") (pintype "passive+no_connect"))
    )
    (net (code "104") (name "unconnected-(J6-NC69-Pad69)") (class "Default")
      (node (ref "J6") (pin "69") (pinfunction "NC69_69") (pintype "passive+no_connect"))
    )
    (net (code "105") (name "unconnected-(J6-NC75-Pad75)") (class "Default")
      (node (ref "J6") (pin "75") (pinfunction "NC75_75") (pintype "passive+no_connect"))
    )
    (net (code "106") (name "unconnected-(J6-VACT_GPS_IN-Pad22)") (class "Default")
      (node (ref "J6") (pin "22") (pinfunction "VACT_GPS_IN_22") (pintype "passive+no_connect"))
    )
    (net (code "107") (name "unconnected-(MOD1-(ARef)-PadJ1.3)") (class "Default")
      (node (ref "MOD1") (pin "J1.3") (pinfunction "(ARef)_J1.3") (pintype "passive"))
    )
    (net (code "108") (name "unconnected-(MOD1-3V-PadJ1.2)") (class "Default")
      (node (ref "MOD1") (pin "J1.2") (pinfunction "3V_J1.2") (pintype "passive"))
    )
    (net (code "109") (name "unconnected-(MOD1-A0-PadJ1.5)") (class "Default")
      (node (ref "MOD1") (pin "J1.5") (pinfunction "A0_J1.5") (pintype "passive"))
    )
    (net (code "110") (name "unconnected-(MOD1-A1-PadJ1.6)") (class "Default")
      (node (ref "MOD1") (pin "J1.6") (pinfunction "A1_J1.6") (pintype "passive"))
    )
    (net (code "111") (name "unconnected-(MOD1-A2-PadJ1.7)") (class "Default")
      (node (ref "MOD1") (pin "J1.7") (pinfunction "A2_J1.7") (pintype "passive"))
    )
    (net (code "112") (name "unconnected-(MOD1-A3-PadJ1.8)") (class "Default")
      (node (ref "MOD1") (pin "J1.8") (pinfunction "A3_J1.8") (pintype "passive"))
    )
    (net (code "113") (name "unconnected-(MOD1-A4-PadJ1.9)") (class "Default")
      (node (ref "MOD1") (pin "J1.9") (pinfunction "A4_J1.9") (pintype "passive"))
    )
    (net (code "114") (name "unconnected-(MOD1-A5-PadJ1.10)") (class "Default")
      (node (ref "MOD1") (pin "J1.10") (pinfunction "A5_J1.10") (pintype "passive"))
    )
    (net (code "115") (name "unconnected-(MOD1-B0-PadJ1.16)") (class "Default")
      (node (ref "MOD1") (pin "J1.16") (pinfunction "B0_J1.16") (pintype "passive"))
    )
    (net (code "116") (name "unconnected-(MOD1-D0(RX)-PadJ1.14)") (class "Default")
      (node (ref "MOD1") (pin "J1.14") (pinfunction "D0(RX)_J1.14") (pintype "passive"))
    )
    (net (code "117") (name "unconnected-(MOD1-D1(TX)-PadJ1.15)") (class "Default")
      (node (ref "MOD1") (pin "J1.15") (pinfunction "D1(TX)_J1.15") (pintype "passive"))
    )
    (net (code "118") (name "unconnected-(MOD1-D5-PadJ3.10)") (class "Default")
      (node (ref "MOD1") (pin "J3.10") (pinfunction "D5_J3.10") (pintype "passive"))
    )
    (net (code "119") (name "unconnected-(MOD1-D6-PadJ3.9)") (class "Default")
      (node (ref "MOD1") (pin "J3.9") (pinfunction "D6_J3.9") (pintype "passive"))
    )
    (net (code "120") (name "unconnected-(MOD1-D9-PadJ3.8)") (class "Default")
      (node (ref "MOD1") (pin "J3.8") (pinfunction "D9_J3.8") (pintype "passive"))
    )
    (net (code "121") (name "unconnected-(MOD1-D10-PadJ3.7)") (class "Default")
      (node (ref "MOD1") (pin "J3.7") (pinfunction "D10_J3.7") (pintype "passive"))
    )
    (net (code "122") (name "unconnected-(MOD1-D11-PadJ3.6)") (class "Default")
      (node (ref "MOD1") (pin "J3.6") (pinfunction "D11_J3.6") (pintype "passive"))
    )
    (net (code "123") (name "unconnected-(MOD1-D12-PadJ3.5)") (class "Default")
      (node (ref "MOD1") (pin "J3.5") (pinfunction "D12_J3.5") (pintype "passive"))
    )
    (net (code "124") (name "unconnected-(MOD1-D13-PadJ3.4)") (class "Default")
      (node (ref "MOD1") (pin "J3.4") (pinfunction "D13_J3.4") (pintype "passive"))
    )
    (net (code "125") (name "unconnected-(MOD1-EN-PadJ3.2)") (class "Default")
      (node (ref "MOD1") (pin "J3.2") (pinfunction "EN_J3.2") (pintype "passive"))
    )
    (net (code "126") (name "unconnected-(MOD1-GND-PadJ1.4)") (class "Default")
      (node (ref "MOD1") (pin "J1.4") (pinfunction "GND_J1.4") (pintype "passive"))
    )
    (net (code "127") (name "unconnected-(MOD1-MISO-PadJ1.13)") (class "Default")
      (node (ref "MOD1") (pin "J1.13") (pinfunction "MISO_J1.13") (pintype "passive"))
    )
    (net (code "128") (name "unconnected-(MOD1-MOSI-PadJ1.12)") (class "Default")
      (node (ref "MOD1") (pin "J1.12") (pinfunction "MOSI_J1.12") (pintype "passive"))
    )
    (net (code "129") (name "unconnected-(MOD1-RESET#-PadJ1.1)") (class "Default")
      (node (ref "MOD1") (pin "J1.1") (pinfunction "RESET#_J1.1") (pintype "passive"))
    )
    (net (code "130") (name "unconnected-(MOD1-SCK-PadJ1.11)") (class "Default")
      (node (ref "MOD1") (pin "J1.11") (pinfunction "SCK_J1.11") (pintype "passive"))
    )
    (net (code "131") (name "unconnected-(MOD1-SCL-PadJ3.11)") (class "Default")
      (node (ref "MOD1") (pin "J3.11") (pinfunction "SCL_J3.11") (pintype "passive"))
    )
    (net (code "132") (name "unconnected-(MOD1-SDA-PadJ3.12)") (class "Default")
      (node (ref "MOD1") (pin "J3.12") (pinfunction "SDA_J3.12") (pintype "passive"))
    )
    (net (code "133") (name "unconnected-(MOD1-VBAT-PadJ3.1)") (class "Default")
      (node (ref "MOD1") (pin "J3.1") (pinfunction "VBAT_J3.1") (pintype "passive"))
    )
    (net (code "134") (name "unconnected-(MOD1-VBUS-PadJ3.3)") (class "Default")
      (node (ref "MOD1") (pin "J3.3") (pinfunction "VBUS_J3.3") (pintype "passive"))
    )
    (net (code "135") (name "unconnected-(MOD1L-Pad2)") (class "Default")
      (node (ref "MOD1L") (pin "2") (pinfunction "2_2") (pintype "passive+no_connect"))
    )
    (net (code "136") (name "unconnected-(RR1-Pad7)") (class "Default")
      (node (ref "RR1") (pin "7") (pinfunction "7_7") (pintype "passive+no_connect"))
    )
    (net (code "137") (name "unconnected-(RR1-Pad8)") (class "Default")
      (node (ref "RR1") (pin "8") (pinfunction "8_8") (pintype "passive+no_connect"))
    )
    (net (code "138") (name "unconnected-(RR2-Pad9)") (class "Default")
      (node (ref "RR2") (pin "9") (pinfunction "9_9") (pintype "passive+no_connect"))
    )
    (net (code "139") (name "unconnected-(RR2-Pad10)") (class "Default")
      (node (ref "RR2") (pin "10") (pinfunction "10_10") (pintype "passive+no_connect"))
    )
  )
)
